# Ryu.net
KiCad netlist of a schematic drawn in Altium Designer
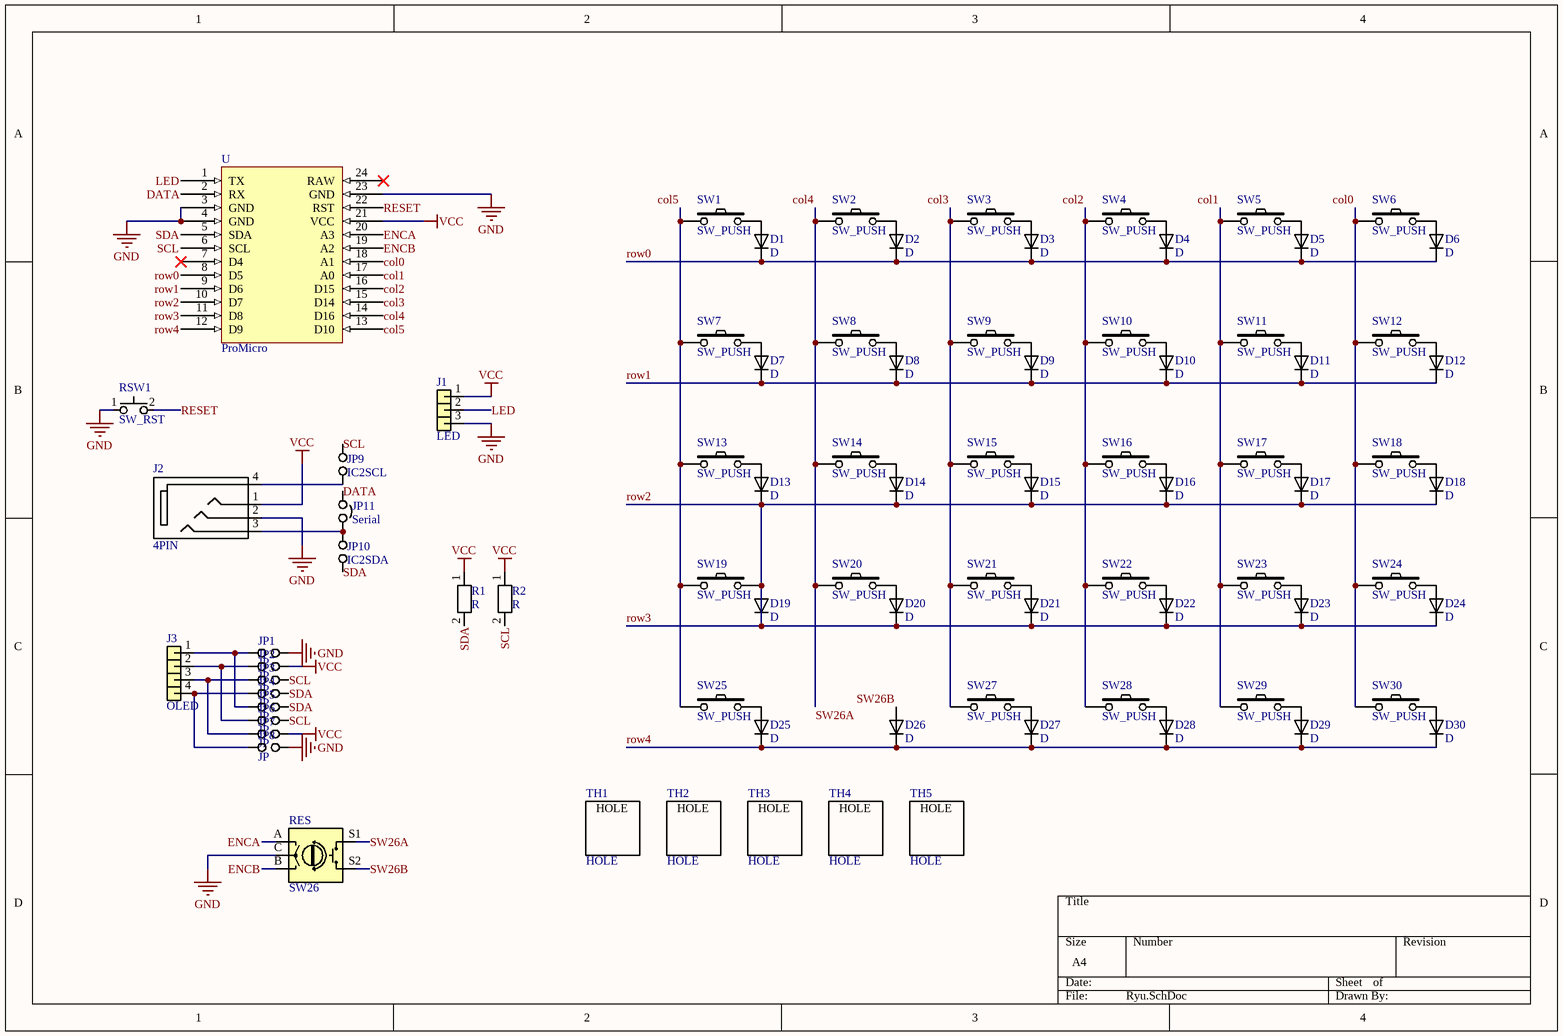
[diagram p0: Ryu.SchDoc]

(export (version "E")
  (design (tool "Eeschema 10.0.6"))
  (components
    (comp (ref "D1") (value "D") (footprint "D_SOD123") (libsource (lib "RyuSch") (part "D")))
    (comp (ref "D2") (value "D") (footprint "D_SOD123") (libsource (lib "RyuSch") (part "D")))
    (comp (ref "D3") (value "D") (footprint "D_SOD123") (libsource (lib "RyuSch") (part "D")))
    (comp (ref "D4") (value "D") (footprint "D_SOD123") (libsource (lib "RyuSch") (part "D")))
    (comp (ref "D5") (value "D") (footprint "D_SOD123") (libsource (lib "RyuSch") (part "D")))
    (comp (ref "D6") (value "D") (footprint "D_SOD123") (libsource (lib "RyuSch") (part "D")))
    (comp (ref "D7") (value "D") (footprint "D_SOD123") (libsource (lib "RyuSch") (part "D")))
    (comp (ref "D8") (value "D") (footprint "D_SOD123") (libsource (lib "RyuSch") (part "D")))
    (comp (ref "D9") (value "D") (footprint "D_SOD123") (libsource (lib "RyuSch") (part "D")))
    (comp (ref "D10") (value "D") (footprint "D_SOD123") (libsource (lib "RyuSch") (part "D")))
    (comp (ref "D11") (value "D") (footprint "D_SOD123") (libsource (lib "RyuSch") (part "D")))
    (comp (ref "D12") (value "D") (footprint "D_SOD123") (libsource (lib "RyuSch") (part "D")))
    (comp (ref "D13") (value "D") (footprint "D_SOD123") (libsource (lib "RyuSch") (part "D")))
    (comp (ref "D14") (value "D") (footprint "D_SOD123") (libsource (lib "RyuSch") (part "D")))
    (comp (ref "D15") (value "D") (footprint "D_SOD123") (libsource (lib "RyuSch") (part "D")))
    (comp (ref "D16") (value "D") (footprint "D_SOD123") (libsource (lib "RyuSch") (part "D")))
    (comp (ref "D17") (value "D") (footprint "D_SOD123") (libsource (lib "RyuSch") (part "D")))
    (comp (ref "D18") (value "D") (footprint "D_SOD123") (libsource (lib "RyuSch") (part "D")))
    (comp (ref "D19") (value "D") (footprint "D_SOD123") (libsource (lib "RyuSch") (part "D")))
    (comp (ref "D20") (value "D") (footprint "D_SOD123") (libsource (lib "RyuSch") (part "D")))
    (comp (ref "D21") (value "D") (footprint "D_SOD123") (libsource (lib "RyuSch") (part "D")))
    (comp (ref "D22") (value "D") (footprint "D_SOD123") (libsource (lib "RyuSch") (part "D")))
    (comp (ref "D23") (value "D") (footprint "D_SOD123") (libsource (lib "RyuSch") (part "D")))
    (comp (ref "D24") (value "D") (footprint "D_SOD123") (libsource (lib "RyuSch") (part "D")))
    (comp (ref "D25") (value "D") (footprint "D_SOD123") (libsource (lib "RyuSch") (part "D")))
    (comp (ref "D26") (value "D") (footprint "D_SOD123") (libsource (lib "RyuSch") (part "D")))
    (comp (ref "D27") (value "D") (footprint "D_SOD123") (libsource (lib "RyuSch") (part "D")))
    (comp (ref "D28") (value "D") (footprint "D_SOD123") (libsource (lib "RyuSch") (part "D")))
    (comp (ref "D29") (value "D") (footprint "D_SOD123") (libsource (lib "RyuSch") (part "D")))
    (comp (ref "D30") (value "D") (footprint "D_SOD123") (libsource (lib "RyuSch") (part "D")))
    (comp (ref "J1") (value "LED") (footprint "LED") (libsource (lib "RyuSch") (part "LED")))
    (comp (ref "J2") (value "4PIN") (footprint "TRRS") (libsource (lib "RyuSch") (part "4PIN")))
    (comp (ref "J3") (value "OLED") (footprint "OLED") (libsource (lib "RyuSch") (part "OLED")))
    (comp (ref "JP1") (value "JP") (footprint "JUMPER") (libsource (lib "RyuSch") (part "JP")))
    (comp (ref "JP2") (value "JP") (footprint "JUMPER") (libsource (lib "RyuSch") (part "JP")))
    (comp (ref "JP3") (value "JP") (footprint "JUMPER") (libsource (lib "RyuSch") (part "JP")))
    (comp (ref "JP4") (value "JP") (footprint "JUMPER") (libsource (lib "RyuSch") (part "JP")))
    (comp (ref "JP5") (value "JP") (footprint "JUMPER") (libsource (lib "RyuSch") (part "JP")))
    (comp (ref "JP6") (value "JP") (footprint "JUMPER") (libsource (lib "RyuSch") (part "JP")))
    (comp (ref "JP7") (value "JP") (footprint "JUMPER") (libsource (lib "RyuSch") (part "JP")))
    (comp (ref "JP8") (value "JP") (footprint "JUMPER") (libsource (lib "RyuSch") (part "JP")))
    (comp (ref "JP9") (value "IC2SCL") (footprint "JUMPER_Triangle") (libsource (lib "RyuSch") (part "JP")))
    (comp (ref "JP10") (value "IC2SDA") (footprint "JUMPER_Triangle") (libsource (lib "RyuSch") (part "JP")))
    (comp (ref "JP11") (value "Serial") (footprint "JUMPER_DATA") (libsource (lib "RyuSch") (part "JP_C")))
    (comp (ref "R1") (value "R") (footprint "RESISTOR") (libsource (lib "RyuSch") (part "R")))
    (comp (ref "R2") (value "R") (footprint "RESISTOR") (libsource (lib "RyuSch") (part "R")))
    (comp (ref "RES") (value "SW26") (footprint "Rotary_Encoder_Alps") (libsource (lib "RyuSch") (part "SW")))
    (comp (ref "RSW1") (value "SW_RST") (footprint "RST_SWITCH") (libsource (lib "RyuSch") (part "SW_RST")))
    (comp (ref "SW1")
      (value "SW_PUSH")
      (footprint "1u-CherryMX-Hotswap-Dualside")
      (libsource (lib "RyuSch") (part "SW_PUSH"))
    )
    (comp (ref "SW2")
      (value "SW_PUSH")
      (footprint "1u-CherryMX-Hotswap-Dualside")
      (libsource (lib "RyuSch") (part "SW_PUSH"))
    )
    (comp (ref "SW3")
      (value "SW_PUSH")
      (footprint "1u-CherryMX-Hotswap-Dualside")
      (libsource (lib "RyuSch") (part "SW_PUSH"))
    )
    (comp (ref "SW4")
      (value "SW_PUSH")
      (footprint "1u-CherryMX-Hotswap-Dualside")
      (libsource (lib "RyuSch") (part "SW_PUSH"))
    )
    (comp (ref "SW5")
      (value "SW_PUSH")
      (footprint "1u-CherryMX-Hotswap-Dualside")
      (libsource (lib "RyuSch") (part "SW_PUSH"))
    )
    (comp (ref "SW6")
      (value "SW_PUSH")
      (footprint "1.5u-CHERRYmx-hotswap-dualside")
      (libsource (lib "RyuSch") (part "SW_PUSH"))
    )
    (comp (ref "SW7")
      (value "SW_PUSH")
      (footprint "1u-CherryMX-Hotswap-Dualside")
      (libsource (lib "RyuSch") (part "SW_PUSH"))
    )
    (comp (ref "SW8")
      (value "SW_PUSH")
      (footprint "1u-CherryMX-Hotswap-Dualside")
      (libsource (lib "RyuSch") (part "SW_PUSH"))
    )
    (comp (ref "SW9")
      (value "SW_PUSH")
      (footprint "1u-CherryMX-Hotswap-Dualside")
      (libsource (lib "RyuSch") (part "SW_PUSH"))
    )
    (comp (ref "SW10")
      (value "SW_PUSH")
      (footprint "1u-CherryMX-Hotswap-Dualside")
      (libsource (lib "RyuSch") (part "SW_PUSH"))
    )
    (comp (ref "SW11")
      (value "SW_PUSH")
      (footprint "1u-CherryMX-Hotswap-Dualside")
      (libsource (lib "RyuSch") (part "SW_PUSH"))
    )
    (comp (ref "SW12")
      (value "SW_PUSH")
      (footprint "1.5u-CHERRYmx-hotswap-dualside")
      (libsource (lib "RyuSch") (part "SW_PUSH"))
    )
    (comp (ref "SW13")
      (value "SW_PUSH")
      (footprint "1u-CherryMX-Hotswap-Dualside")
      (libsource (lib "RyuSch") (part "SW_PUSH"))
    )
    (comp (ref "SW14")
      (value "SW_PUSH")
      (footprint "1u-CherryMX-Hotswap-Dualside")
      (libsource (lib "RyuSch") (part "SW_PUSH"))
    )
    (comp (ref "SW15")
      (value "SW_PUSH")
      (footprint "1u-CherryMX-Hotswap-Dualside")
      (libsource (lib "RyuSch") (part "SW_PUSH"))
    )
    (comp (ref "SW16")
      (value "SW_PUSH")
      (footprint "1u-CherryMX-Hotswap-Dualside")
      (libsource (lib "RyuSch") (part "SW_PUSH"))
    )
    (comp (ref "SW17")
      (value "SW_PUSH")
      (footprint "1u-CherryMX-Hotswap-Dualside")
      (libsource (lib "RyuSch") (part "SW_PUSH"))
    )
    (comp (ref "SW18")
      (value "SW_PUSH")
      (footprint "1.5u-CHERRYmx-hotswap-dualside")
      (libsource (lib "RyuSch") (part "SW_PUSH"))
    )
    (comp (ref "SW19")
      (value "SW_PUSH")
      (footprint "1u-CherryMX-Hotswap-Dualside")
      (libsource (lib "RyuSch") (part "SW_PUSH"))
    )
    (comp (ref "SW20")
      (value "SW_PUSH")
      (footprint "1u-CherryMX-Hotswap-Dualside")
      (libsource (lib "RyuSch") (part "SW_PUSH"))
    )
    (comp (ref "SW21")
      (value "SW_PUSH")
      (footprint "1u-CherryMX-Hotswap-Dualside")
      (libsource (lib "RyuSch") (part "SW_PUSH"))
    )
    (comp (ref "SW22")
      (value "SW_PUSH")
      (footprint "1u-CherryMX-Hotswap-Dualside")
      (libsource (lib "RyuSch") (part "SW_PUSH"))
    )
    (comp (ref "SW23")
      (value "SW_PUSH")
      (footprint "1u-CherryMX-Hotswap-Dualside")
      (libsource (lib "RyuSch") (part "SW_PUSH"))
    )
    (comp (ref "SW24")
      (value "SW_PUSH")
      (footprint "1.5u-CHERRYmx-hotswap-dualside")
      (libsource (lib "RyuSch") (part "SW_PUSH"))
    )
    (comp (ref "SW25")
      (value "SW_PUSH")
      (footprint "1u-CherryMX-Hotswap-Dualside")
      (libsource (lib "RyuSch") (part "SW_PUSH"))
    )
    (comp (ref "SW27")
      (value "SW_PUSH")
      (footprint "1.5u-CHERRYmx-hotswap-dualside")
      (libsource (lib "RyuSch") (part "SW_PUSH"))
    )
    (comp (ref "SW28")
      (value "SW_PUSH")
      (footprint "1u-CherryMX-Hotswap-Dualside")
      (libsource (lib "RyuSch") (part "SW_PUSH"))
    )
    (comp (ref "SW29")
      (value "SW_PUSH")
      (footprint "1u-CherryMX-Hotswap-Dualside")
      (libsource (lib "RyuSch") (part "SW_PUSH"))
    )
    (comp (ref "SW30")
      (value "SW_PUSH")
      (footprint "1u-CherryMX-Hotswap-Dualside")
      (libsource (lib "RyuSch") (part "SW_PUSH"))
    )
    (comp (ref "TH1") (value "HOLE") (footprint "M2_TH_HOLE") (libsource (lib "RyuSch") (part "HOLE")))
    (comp (ref "TH2") (value "HOLE") (footprint "M2_TH_HOLE") (libsource (lib "RyuSch") (part "HOLE")))
    (comp (ref "TH3") (value "HOLE") (footprint "M2_TH_HOLE") (libsource (lib "RyuSch") (part "HOLE")))
    (comp (ref "TH4") (value "HOLE") (footprint "M2_TH_HOLE") (libsource (lib "RyuSch") (part "HOLE")))
    (comp (ref "TH5") (value "HOLE") (footprint "M2_TH_HOLE") (libsource (lib "RyuSch") (part "HOLE")))
    (comp (ref "U") (value "ProMicro") (footprint "ProMicro") (libsource (lib "RyuSch") (part "ProMicro")))
  )
  (nets
    (net (code "1") (name "/DATA") (class "Default")
      (node (ref "JP11") (pin "J1") (pinfunction "28_J1") (pintype "passive"))
      (node (ref "U") (pin "2") (pinfunction "RX_2") (pintype "input"))
    )
    (net (code "2") (name "/ENCA") (class "Default")
      (node (ref "RES") (pin "A") (pinfunction "A_A") (pintype "passive"))
      (node (ref "U") (pin "20") (pinfunction "A3_20") (pintype "input"))
    )
    (net (code "3") (name "/ENCB") (class "Default")
      (node (ref "RES") (pin "B") (pinfunction "C_B") (pintype "passive"))
      (node (ref "U") (pin "19") (pinfunction "A2_19") (pintype "input"))
    )
    (net (code "4") (name "/LED") (class "Default")
      (node (ref "J1") (pin "2") (pinfunction "16_2") (pintype "passive"))
      (node (ref "U") (pin "1") (pinfunction "TX_1") (pintype "input"))
    )
    (net (code "5") (name "/RESET") (class "Default")
      (node (ref "RSW1") (pin "2") (pinfunction "12_2") (pintype "passive"))
      (node (ref "U") (pin "22") (pinfunction "RST_22") (pintype "input"))
    )
    (net (code "6") (name "/SCL") (class "Default")
      (node (ref "JP3") (pin "J2") (pinfunction "27_J2") (pintype "passive"))
      (node (ref "JP6") (pin "J2") (pinfunction "27_J2") (pintype "passive"))
      (node (ref "JP9") (pin "J2") (pinfunction "27_J2") (pintype "passive"))
      (node (ref "R2") (pin "2") (pinfunction "5_2") (pintype "passive"))
      (node (ref "U") (pin "6") (pinfunction "SCL_6") (pintype "input"))
    )
    (net (code "7") (name "/SDA") (class "Default")
      (node (ref "JP10") (pin "J2") (pinfunction "27_J2") (pintype "passive"))
      (node (ref "JP4") (pin "J2") (pinfunction "27_J2") (pintype "passive"))
      (node (ref "JP5") (pin "J2") (pinfunction "27_J2") (pintype "passive"))
      (node (ref "R1") (pin "2") (pinfunction "5_2") (pintype "passive"))
      (node (ref "U") (pin "5") (pinfunction "SDA_5") (pintype "input"))
    )
    (net (code "8") (name "/SW26A") (class "Default")
      (node (ref "RES") (pin "S1") (pinfunction "8_S1") (pintype "passive"))
      (node (ref "SW14") (pin "1") (pinfunction "1_1") (pintype "passive"))
      (node (ref "SW2") (pin "1") (pinfunction "1_1") (pintype "passive"))
      (node (ref "SW20") (pin "1") (pinfunction "1_1") (pintype "passive"))
      (node (ref "SW8") (pin "1") (pinfunction "1_1") (pintype "passive"))
      (node (ref "U") (pin "14") (pinfunction "D16_14") (pintype "input"))
    )
    (net (code "9") (name "/SW26B") (class "Default")
      (node (ref "D26") (pin "2") (pinfunction "A_2") (pintype "passive"))
      (node (ref "RES") (pin "S2") (pinfunction "9_S2") (pintype "passive"))
    )
    (net (code "10") (name "/col0") (class "Default")
      (node (ref "SW12") (pin "1") (pinfunction "1_1") (pintype "passive"))
      (node (ref "SW18") (pin "1") (pinfunction "1_1") (pintype "passive"))
      (node (ref "SW24") (pin "1") (pinfunction "1_1") (pintype "passive"))
      (node (ref "SW30") (pin "1") (pinfunction "1_1") (pintype "passive"))
      (node (ref "SW6") (pin "1") (pinfunction "1_1") (pintype "passive"))
      (node (ref "U") (pin "18") (pinfunction "A1_18") (pintype "input"))
    )
    (net (code "11") (name "/col1") (class "Default")
      (node (ref "SW11") (pin "1") (pinfunction "1_1") (pintype "passive"))
      (node (ref "SW17") (pin "1") (pinfunction "1_1") (pintype "passive"))
      (node (ref "SW23") (pin "1") (pinfunction "1_1") (pintype "passive"))
      (node (ref "SW29") (pin "1") (pinfunction "1_1") (pintype "passive"))
      (node (ref "SW5") (pin "1") (pinfunction "1_1") (pintype "passive"))
      (node (ref "U") (pin "17") (pinfunction "A0_17") (pintype "input"))
    )
    (net (code "12") (name "/col2") (class "Default")
      (node (ref "SW10") (pin "1") (pinfunction "1_1") (pintype "passive"))
      (node (ref "SW16") (pin "1") (pinfunction "1_1") (pintype "passive"))
      (node (ref "SW22") (pin "1") (pinfunction "1_1") (pintype "passive"))
      (node (ref "SW28") (pin "1") (pinfunction "1_1") (pintype "passive"))
      (node (ref "SW4") (pin "1") (pinfunction "1_1") (pintype "passive"))
      (node (ref "U") (pin "16") (pinfunction "D15_16") (pintype "input"))
    )
    (net (code "13") (name "/col3") (class "Default")
      (node (ref "SW15") (pin "1") (pinfunction "1_1") (pintype "passive"))
      (node (ref "SW21") (pin "1") (pinfunction "1_1") (pintype "passive"))
      (node (ref "SW27") (pin "1") (pinfunction "1_1") (pintype "passive"))
      (node (ref "SW3") (pin "1") (pinfunction "1_1") (pintype "passive"))
      (node (ref "SW9") (pin "1") (pinfunction "1_1") (pintype "passive"))
      (node (ref "U") (pin "15") (pinfunction "D14_15") (pintype "input"))
    )
    (net (code "14") (name "/col5") (class "Default")
      (node (ref "SW1") (pin "1") (pinfunction "1_1") (pintype "passive"))
      (node (ref "SW13") (pin "1") (pinfunction "1_1") (pintype "passive"))
      (node (ref "SW19") (pin "1") (pinfunction "1_1") (pintype "passive"))
      (node (ref "SW25") (pin "1") (pinfunction "1_1") (pintype "passive"))
      (node (ref "SW7") (pin "1") (pinfunction "1_1") (pintype "passive"))
      (node (ref "U") (pin "13") (pinfunction "D10_13") (pintype "input"))
    )
    (net (code "15") (name "/row0") (class "Default")
      (node (ref "D1") (pin "1") (pinfunction "K_1") (pintype "passive"))
      (node (ref "D2") (pin "1") (pinfunction "K_1") (pintype "passive"))
      (node (ref "D3") (pin "1") (pinfunction "K_1") (pintype "passive"))
      (node (ref "D4") (pin "1") (pinfunction "K_1") (pintype "passive"))
      (node (ref "D5") (pin "1") (pinfunction "K_1") (pintype "passive"))
      (node (ref "D6") (pin "1") (pinfunction "K_1") (pintype "passive"))
      (node (ref "U") (pin "8") (pinfunction "D5_8") (pintype "input"))
    )
    (net (code "16") (name "/row1") (class "Default")
      (node (ref "D10") (pin "1") (pinfunction "K_1") (pintype "passive"))
      (node (ref "D11") (pin "1") (pinfunction "K_1") (pintype "passive"))
      (node (ref "D12") (pin "1") (pinfunction "K_1") (pintype "passive"))
      (node (ref "D7") (pin "1") (pinfunction "K_1") (pintype "passive"))
      (node (ref "D8") (pin "1") (pinfunction "K_1") (pintype "passive"))
      (node (ref "D9") (pin "1") (pinfunction "K_1") (pintype "passive"))
      (node (ref "U") (pin "9") (pinfunction "D6_9") (pintype "input"))
    )
    (net (code "17") (name "/row2") (class "Default")
      (node (ref "D13") (pin "1") (pinfunction "K_1") (pintype "passive"))
      (node (ref "D14") (pin "1") (pinfunction "K_1") (pintype "passive"))
      (node (ref "D15") (pin "1") (pinfunction "K_1") (pintype "passive"))
      (node (ref "D16") (pin "1") (pinfunction "K_1") (pintype "passive"))
      (node (ref "D17") (pin "1") (pinfunction "K_1") (pintype "passive"))
      (node (ref "D18") (pin "1") (pinfunction "K_1") (pintype "passive"))
      (node (ref "D19") (pin "1") (pinfunction "K_1") (pintype "passive"))
      (node (ref "D19") (pin "2") (pinfunction "A_2") (pintype "passive"))
      (node (ref "D20") (pin "1") (pinfunction "K_1") (pintype "passive"))
      (node (ref "D21") (pin "1") (pinfunction "K_1") (pintype "passive"))
      (node (ref "D22") (pin "1") (pinfunction "K_1") (pintype "passive"))
      (node (ref "D23") (pin "1") (pinfunction "K_1") (pintype "passive"))
      (node (ref "D24") (pin "1") (pinfunction "K_1") (pintype "passive"))
      (node (ref "SW19") (pin "2") (pinfunction "2_2") (pintype "passive"))
      (node (ref "U") (pin "10") (pinfunction "D7_10") (pintype "input"))
      (node (ref "U") (pin "11") (pinfunction "D8_11") (pintype "input"))
    )
    (net (code "18") (name "/row4") (class "Default")
      (node (ref "D25") (pin "1") (pinfunction "K_1") (pintype "passive"))
      (node (ref "D26") (pin "1") (pinfunction "K_1") (pintype "passive"))
      (node (ref "D27") (pin "1") (pinfunction "K_1") (pintype "passive"))
      (node (ref "D28") (pin "1") (pinfunction "K_1") (pintype "passive"))
      (node (ref "D29") (pin "1") (pinfunction "K_1") (pintype "passive"))
      (node (ref "D30") (pin "1") (pinfunction "K_1") (pintype "passive"))
      (node (ref "U") (pin "12") (pinfunction "D9_12") (pintype "input"))
    )
    (net (code "19") (name "GND") (class "Default")
      (node (ref "J1") (pin "3") (pinfunction "17_3") (pintype "passive"))
      (node (ref "J2") (pin "2") (pinfunction "21_2") (pintype "passive"))
      (node (ref "JP1") (pin "J2") (pinfunction "27_J2") (pintype "passive"))
      (node (ref "JP8") (pin "J2") (pinfunction "27_J2") (pintype "passive"))
      (node (ref "RES") (pin "C") (pinfunction "B_C") (pintype "passive"))
      (node (ref "RSW1") (pin "1") (pinfunction "13_1") (pintype "passive"))
      (node (ref "U") (pin "23") (pinfunction "GND_23") (pintype "input"))
      (node (ref "U") (pin "3") (pinfunction "GND_3") (pintype "input"))
      (node (ref "U") (pin "4") (pinfunction "GND_4") (pintype "input"))
    )
    (net (code "20") (name "Net-(D1-A)") (class "Default")
      (node (ref "D1") (pin "2") (pinfunction "A_2") (pintype "passive"))
      (node (ref "SW1") (pin "2") (pinfunction "2_2") (pintype "passive"))
    )
    (net (code "21") (name "Net-(D2-A)") (class "Default")
      (node (ref "D2") (pin "2") (pinfunction "A_2") (pintype "passive"))
      (node (ref "SW2") (pin "2") (pinfunction "2_2") (pintype "passive"))
    )
    (net (code "22") (name "Net-(D3-A)") (class "Default")
      (node (ref "D3") (pin "2") (pinfunction "A_2") (pintype "passive"))
      (node (ref "SW3") (pin "2") (pinfunction "2_2") (pintype "passive"))
    )
    (net (code "23") (name "Net-(D4-A)") (class "Default")
      (node (ref "D4") (pin "2") (pinfunction "A_2") (pintype "passive"))
      (node (ref "SW4") (pin "2") (pinfunction "2_2") (pintype "passive"))
    )
    (net (code "24") (name "Net-(D5-A)") (class "Default")
      (node (ref "D5") (pin "2") (pinfunction "A_2") (pintype "passive"))
      (node (ref "SW5") (pin "2") (pinfunction "2_2") (pintype "passive"))
    )
    (net (code "25") (name "Net-(D6-A)") (class "Default")
      (node (ref "D6") (pin "2") (pinfunction "A_2") (pintype "passive"))
      (node (ref "SW6") (pin "2") (pinfunction "2_2") (pintype "passive"))
    )
    (net (code "26") (name "Net-(D7-A)") (class "Default")
      (node (ref "D7") (pin "2") (pinfunction "A_2") (pintype "passive"))
      (node (ref "SW7") (pin "2") (pinfunction "2_2") (pintype "passive"))
    )
    (net (code "27") (name "Net-(D8-A)") (class "Default")
      (node (ref "D8") (pin "2") (pinfunction "A_2") (pintype "passive"))
      (node (ref "SW8") (pin "2") (pinfunction "2_2") (pintype "passive"))
    )
    (net (code "28") (name "Net-(D9-A)") (class "Default")
      (node (ref "D9") (pin "2") (pinfunction "A_2") (pintype "passive"))
      (node (ref "SW9") (pin "2") (pinfunction "2_2") (pintype "passive"))
    )
    (net (code "29") (name "Net-(D10-A)") (class "Default")
      (node (ref "D10") (pin "2") (pinfunction "A_2") (pintype "passive"))
      (node (ref "SW10") (pin "2") (pinfunction "2_2") (pintype "passive"))
    )
    (net (code "30") (name "Net-(D11-A)") (class "Default")
      (node (ref "D11") (pin "2") (pinfunction "A_2") (pintype "passive"))
      (node (ref "SW11") (pin "2") (pinfunction "2_2") (pintype "passive"))
    )
    (net (code "31") (name "Net-(D12-A)") (class "Default")
      (node (ref "D12") (pin "2") (pinfunction "A_2") (pintype "passive"))
      (node (ref "SW12") (pin "2") (pinfunction "2_2") (pintype "passive"))
    )
    (net (code "32") (name "Net-(D13-A)") (class "Default")
      (node (ref "D13") (pin "2") (pinfunction "A_2") (pintype "passive"))
      (node (ref "SW13") (pin "2") (pinfunction "2_2") (pintype "passive"))
    )
    (net (code "33") (name "Net-(D14-A)") (class "Default")
      (node (ref "D14") (pin "2") (pinfunction "A_2") (pintype "passive"))
      (node (ref "SW14") (pin "2") (pinfunction "2_2") (pintype "passive"))
    )
    (net (code "34") (name "Net-(D15-A)") (class "Default")
      (node (ref "D15") (pin "2") (pinfunction "A_2") (pintype "passive"))
      (node (ref "SW15") (pin "2") (pinfunction "2_2") (pintype "passive"))
    )
    (net (code "35") (name "Net-(D16-A)") (class "Default")
      (node (ref "D16") (pin "2") (pinfunction "A_2") (pintype "passive"))
      (node (ref "SW16") (pin "2") (pinfunction "2_2") (pintype "passive"))
    )
    (net (code "36") (name "Net-(D17-A)") (class "Default")
      (node (ref "D17") (pin "2") (pinfunction "A_2") (pintype "passive"))
      (node (ref "SW17") (pin "2") (pinfunction "2_2") (pintype "passive"))
    )
    (net (code "37") (name "Net-(D18-A)") (class "Default")
      (node (ref "D18") (pin "2") (pinfunction "A_2") (pintype "passive"))
      (node (ref "SW18") (pin "2") (pinfunction "2_2") (pintype "passive"))
    )
    (net (code "38") (name "Net-(D20-A)") (class "Default")
      (node (ref "D20") (pin "2") (pinfunction "A_2") (pintype "passive"))
      (node (ref "SW20") (pin "2") (pinfunction "2_2") (pintype "passive"))
    )
    (net (code "39") (name "Net-(D21-A)") (class "Default")
      (node (ref "D21") (pin "2") (pinfunction "A_2") (pintype "passive"))
      (node (ref "SW21") (pin "2") (pinfunction "2_2") (pintype "passive"))
    )
    (net (code "40") (name "Net-(D22-A)") (class "Default")
      (node (ref "D22") (pin "2") (pinfunction "A_2") (pintype "passive"))
      (node (ref "SW22") (pin "2") (pinfunction "2_2") (pintype "passive"))
    )
    (net (code "41") (name "Net-(D23-A)") (class "Default")
      (node (ref "D23") (pin "2") (pinfunction "A_2") (pintype "passive"))
      (node (ref "SW23") (pin "2") (pinfunction "2_2") (pintype "passive"))
    )
    (net (code "42") (name "Net-(D24-A)") (class "Default")
      (node (ref "D24") (pin "2") (pinfunction "A_2") (pintype "passive"))
      (node (ref "SW24") (pin "2") (pinfunction "2_2") (pintype "passive"))
    )
    (net (code "43") (name "Net-(D25-A)") (class "Default")
      (node (ref "D25") (pin "2") (pinfunction "A_2") (pintype "passive"))
      (node (ref "SW25") (pin "2") (pinfunction "2_2") (pintype "passive"))
    )
    (net (code "44") (name "Net-(D27-A)") (class "Default")
      (node (ref "D27") (pin "2") (pinfunction "A_2") (pintype "passive"))
      (node (ref "SW27") (pin "2") (pinfunction "2_2") (pintype "passive"))
    )
    (net (code "45") (name "Net-(D28-A)") (class "Default")
      (node (ref "D28") (pin "2") (pinfunction "A_2") (pintype "passive"))
      (node (ref "SW28") (pin "2") (pinfunction "2_2") (pintype "passive"))
    )
    (net (code "46") (name "Net-(D29-A)") (class "Default")
      (node (ref "D29") (pin "2") (pinfunction "A_2") (pintype "passive"))
      (node (ref "SW29") (pin "2") (pinfunction "2_2") (pintype "passive"))
    )
    (net (code "47") (name "Net-(D30-A)") (class "Default")
      (node (ref "D30") (pin "2") (pinfunction "A_2") (pintype "passive"))
      (node (ref "SW30") (pin "2") (pinfunction "2_2") (pintype "passive"))
    )
    (net (code "48") (name "Net-(J2-19)") (class "Default")
      (node (ref "J2") (pin "4") (pinfunction "19_4") (pintype "passive"))
      (node (ref "JP9") (pin "J1") (pinfunction "28_J1") (pintype "passive"))
    )
    (net (code "49") (name "Net-(J2-22)") (class "Default")
      (node (ref "J2") (pin "3") (pinfunction "22_3") (pintype "passive"))
      (node (ref "JP10") (pin "J1") (pinfunction "28_J1") (pintype "passive"))
      (node (ref "JP11") (pin "J2") (pinfunction "27_J2") (pintype "passive"))
    )
    (net (code "50") (name "Net-(JP1-28)") (class "Default")
      (node (ref "J3") (pin "1") (pintype "passive"))
      (node (ref "JP1") (pin "J1") (pinfunction "28_J1") (pintype "passive"))
      (node (ref "JP5") (pin "J1") (pinfunction "28_J1") (pintype "passive"))
    )
    (net (code "51") (name "Net-(JP2-28)") (class "Default")
      (node (ref "J3") (pin "2") (pintype "passive"))
      (node (ref "JP2") (pin "J1") (pinfunction "28_J1") (pintype "passive"))
      (node (ref "JP6") (pin "J1") (pinfunction "28_J1") (pintype "passive"))
    )
    (net (code "52") (name "Net-(JP3-28)") (class "Default")
      (node (ref "J3") (pin "3") (pintype "passive"))
      (node (ref "JP3") (pin "J1") (pinfunction "28_J1") (pintype "passive"))
      (node (ref "JP7") (pin "J1") (pinfunction "28_J1") (pintype "passive"))
    )
    (net (code "53") (name "Net-(JP4-28)") (class "Default")
      (node (ref "J3") (pin "4") (pintype "passive"))
      (node (ref "JP4") (pin "J1") (pinfunction "28_J1") (pintype "passive"))
      (node (ref "JP8") (pin "J1") (pinfunction "28_J1") (pintype "passive"))
    )
    (net (code "54") (name "VCC") (class "Default")
      (node (ref "J1") (pin "1") (pinfunction "15_1") (pintype "passive"))
      (node (ref "J2") (pin "1") (pinfunction "20_1") (pintype "passive"))
      (node (ref "JP2") (pin "J2") (pinfunction "27_J2") (pintype "passive"))
      (node (ref "JP7") (pin "J2") (pinfunction "27_J2") (pintype "passive"))
      (node (ref "R1") (pin "1") (pinfunction "11_1") (pintype "passive"))
      (node (ref "R2") (pin "1") (pinfunction "11_1") (pintype "passive"))
      (node (ref "U") (pin "21") (pinfunction "VCC_21") (pintype "input"))
    )
    (net (code "55") (name "unconnected-(U-D4-Pad7)") (class "Default")
      (node (ref "U") (pin "7") (pinfunction "D4_7") (pintype "input+no_connect"))
    )
    (net (code "56") (name "unconnected-(U-RAW-Pad24)") (class "Default")
      (node (ref "U") (pin "24") (pinfunction "RAW_24") (pintype "input+no_connect"))
    )
  )
)
